# m_airconditioner_SCH.net
KiCad netlist of a schematic drawn in Altium Designer
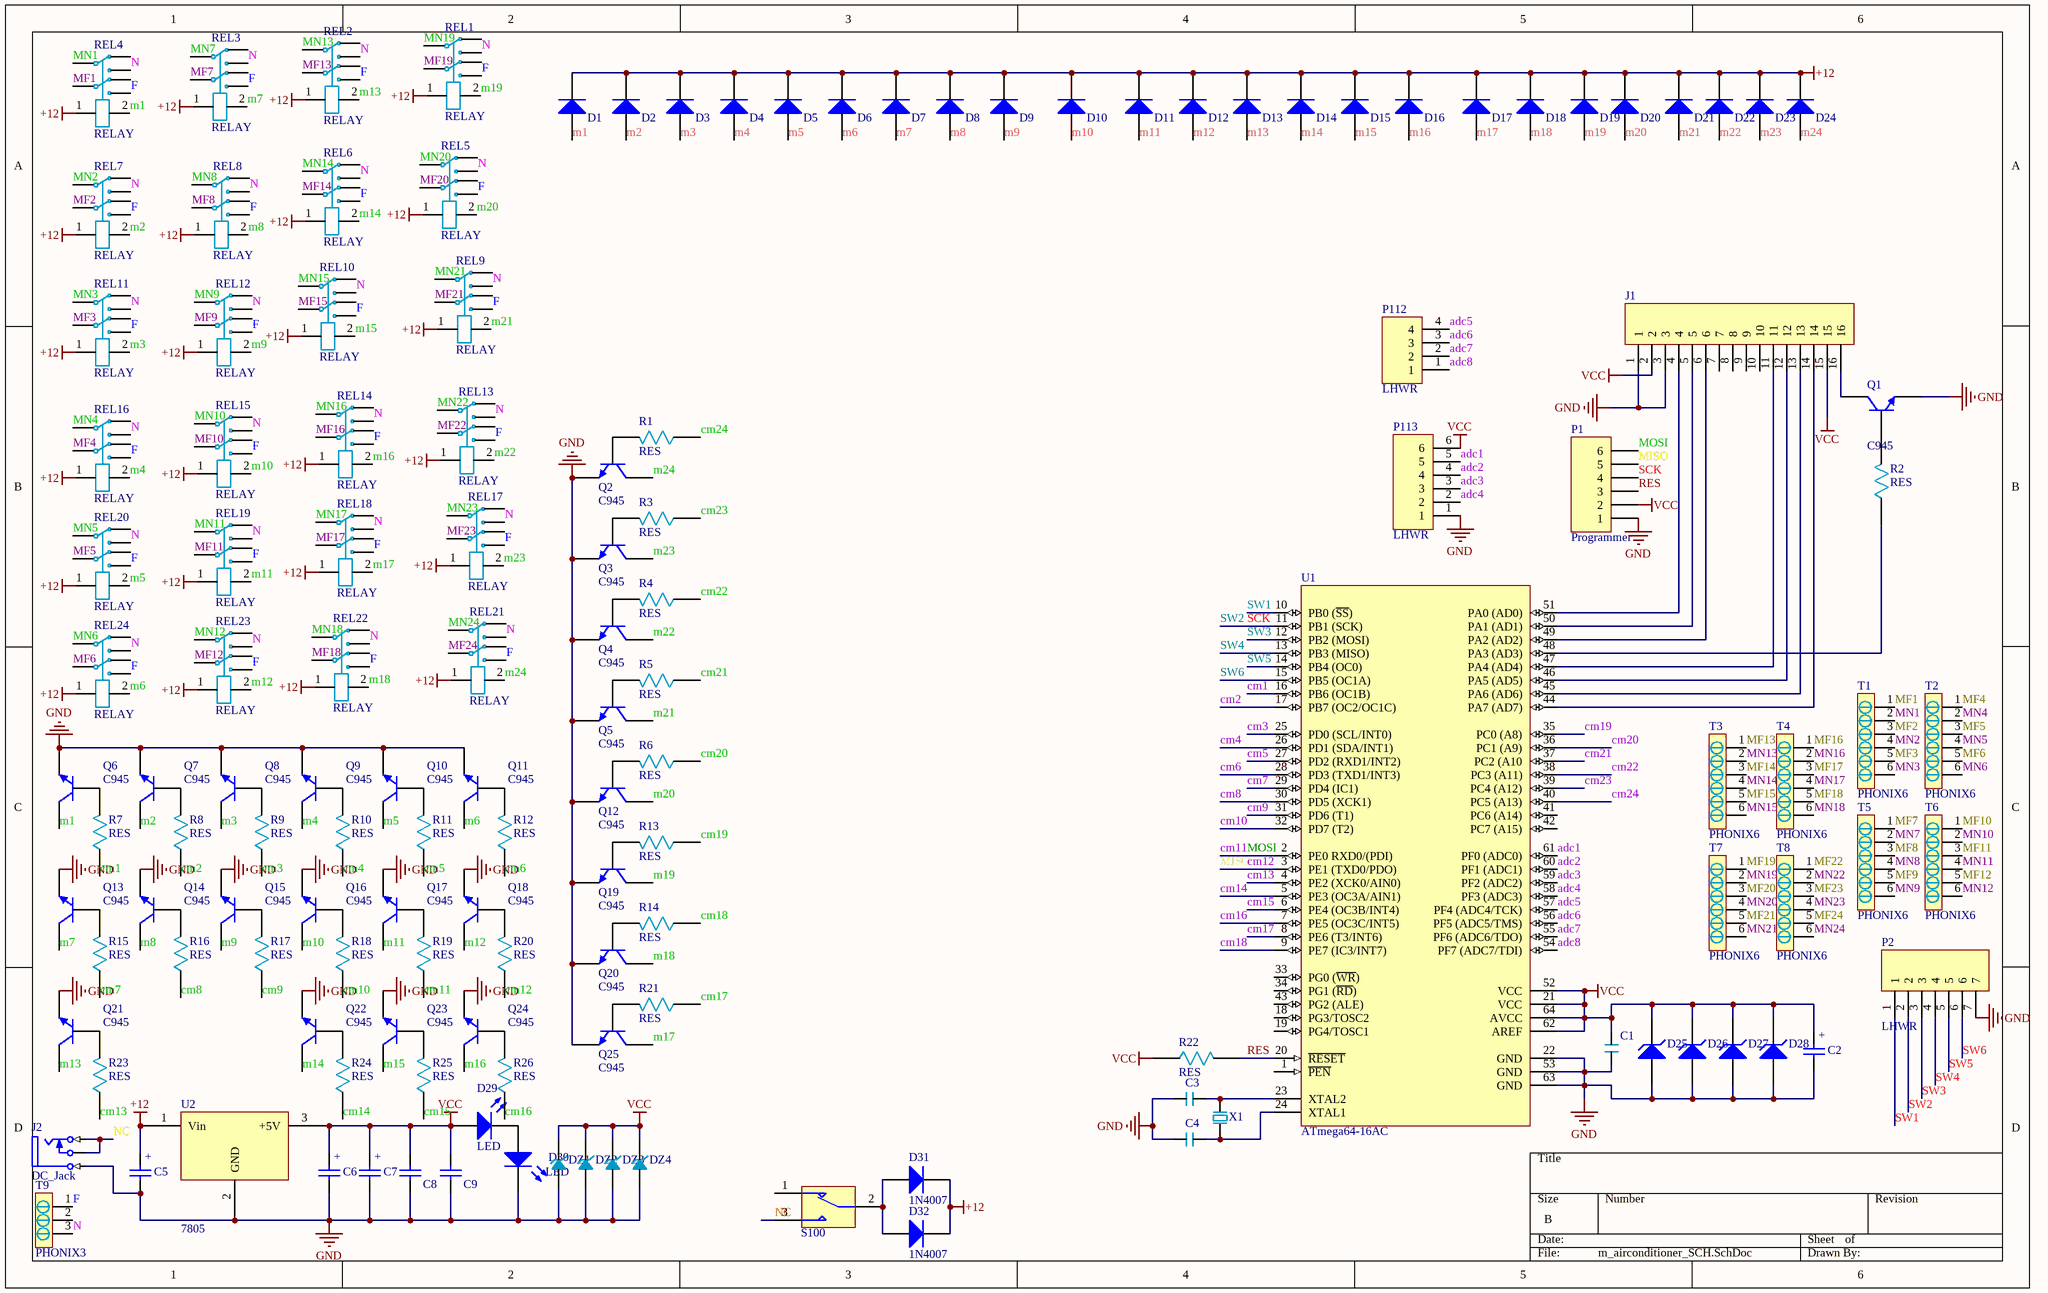
[diagram p0: m_airconditioner_SCH.SchDoc]

(export (version "E")
  (design (tool "Eeschema 10.0.6"))
  (components
    (comp (ref "C1") (value "~") (footprint "RAD_ADA") (libsource (lib "MyAltiumLib") (part "CAP")))
    (comp (ref "C2")
      (value "Cap")
      (footprint "My_cap3300u")
      (description "CAP-3300Uf")
      (libsource (lib "MyAltiumLib1") (part "Cap Pol"))
    )
    (comp (ref "C3") (value "CAP") (footprint "RAD_ADA") (libsource (lib "MyAltiumLib") (part "CAP")))
    (comp (ref "C4") (value "CAP") (footprint "RAD_ADA") (libsource (lib "MyAltiumLib") (part "CAP")))
    (comp (ref "C5")
      (value "Cap")
      (footprint "My_cap3300u")
      (description "CAP-3300Uf")
      (libsource (lib "MyAltiumLib1") (part "Cap Pol"))
    )
    (comp (ref "C6")
      (value "Cap")
      (footprint "My_cap3300u")
      (description "CAP-3300Uf")
      (libsource (lib "MyAltiumLib1") (part "Cap Pol"))
    )
    (comp (ref "C7")
      (value "Cap")
      (footprint "My_cap3300u")
      (description "CAP-3300Uf")
      (libsource (lib "MyAltiumLib1") (part "Cap Pol"))
    )
    (comp (ref "C8")
      (value "Cap")
      (footprint "My_cap100n")
      (description "CAP-100Nf")
      (libsource (lib "MyAltiumLib1") (part "Cap ceramic"))
    )
    (comp (ref "C9")
      (value "Cap")
      (footprint "My_cap100n")
      (description "CAP-100Nf")
      (libsource (lib "MyAltiumLib1") (part "Cap ceramic"))
    )
    (comp (ref "D1")
      (value "1N4007")
      (footprint "My_DO-41")
      (description "1 Amp Diode")
      (libsource (lib "MyAltiumLib1") (part "1N4007"))
    )
    (comp (ref "D2")
      (value "1N4007")
      (footprint "My_DO-41")
      (description "1 Amp Diode")
      (libsource (lib "MyAltiumLib1") (part "1N4007"))
    )
    (comp (ref "D3")
      (value "1N4007")
      (footprint "My_DO-41")
      (description "1 Amp Diode")
      (libsource (lib "MyAltiumLib1") (part "1N4007"))
    )
    (comp (ref "D4")
      (value "1N4007")
      (footprint "My_DO-41")
      (description "1 Amp Diode")
      (libsource (lib "MyAltiumLib1") (part "1N4007"))
    )
    (comp (ref "D5")
      (value "1N4007")
      (footprint "My_DO-41")
      (description "1 Amp Diode")
      (libsource (lib "MyAltiumLib1") (part "1N4007"))
    )
    (comp (ref "D6")
      (value "1N4007")
      (footprint "My_DO-41")
      (description "1 Amp Diode")
      (libsource (lib "MyAltiumLib1") (part "1N4007"))
    )
    (comp (ref "D7")
      (value "1N4007")
      (footprint "My_DO-41")
      (description "1 Amp Diode")
      (libsource (lib "MyAltiumLib1") (part "1N4007"))
    )
    (comp (ref "D8")
      (value "1N4007")
      (footprint "My_DO-41")
      (description "1 Amp Diode")
      (libsource (lib "MyAltiumLib1") (part "1N4007"))
    )
    (comp (ref "D9")
      (value "1N4007")
      (footprint "My_DO-41")
      (description "1 Amp Diode")
      (libsource (lib "MyAltiumLib1") (part "1N4007"))
    )
    (comp (ref "D10")
      (value "1N4007")
      (footprint "My_DO-41")
      (description "1 Amp Diode")
      (libsource (lib "MyAltiumLib1") (part "1N4007"))
    )
    (comp (ref "D11")
      (value "1N4007")
      (footprint "My_DO-41")
      (description "1 Amp Diode")
      (libsource (lib "MyAltiumLib1") (part "1N4007"))
    )
    (comp (ref "D12")
      (value "1N4007")
      (footprint "My_DO-41")
      (description "1 Amp Diode")
      (libsource (lib "MyAltiumLib1") (part "1N4007"))
    )
    (comp (ref "D13")
      (value "1N4007")
      (footprint "My_DO-41")
      (description "1 Amp Diode")
      (libsource (lib "MyAltiumLib1") (part "1N4007"))
    )
    (comp (ref "D14")
      (value "1N4007")
      (footprint "My_DO-41")
      (description "1 Amp Diode")
      (libsource (lib "MyAltiumLib1") (part "1N4007"))
    )
    (comp (ref "D15")
      (value "1N4007")
      (footprint "My_DO-41")
      (description "1 Amp Diode")
      (libsource (lib "MyAltiumLib1") (part "1N4007"))
    )
    (comp (ref "D16")
      (value "1N4007")
      (footprint "My_DO-41")
      (description "1 Amp Diode")
      (libsource (lib "MyAltiumLib1") (part "1N4007"))
    )
    (comp (ref "D17")
      (value "1N4007")
      (footprint "My_DO-41")
      (description "1 Amp Diode")
      (libsource (lib "MyAltiumLib1") (part "1N4007"))
    )
    (comp (ref "D18")
      (value "1N4007")
      (footprint "My_DO-41")
      (description "1 Amp Diode")
      (libsource (lib "MyAltiumLib1") (part "1N4007"))
    )
    (comp (ref "D19")
      (value "1N4007")
      (footprint "My_DO-41")
      (description "1 Amp Diode")
      (libsource (lib "MyAltiumLib1") (part "1N4007"))
    )
    (comp (ref "D20")
      (value "1N4007")
      (footprint "My_DO-41")
      (description "1 Amp Diode")
      (libsource (lib "MyAltiumLib1") (part "1N4007"))
    )
    (comp (ref "D21")
      (value "1N4007")
      (footprint "My_DO-41")
      (description "1 Amp Diode")
      (libsource (lib "MyAltiumLib1") (part "1N4007"))
    )
    (comp (ref "D22")
      (value "1N4007")
      (footprint "My_DO-41")
      (description "1 Amp Diode")
      (libsource (lib "MyAltiumLib1") (part "1N4007"))
    )
    (comp (ref "D23")
      (value "1N4007")
      (footprint "My_DO-41")
      (description "1 Amp Diode")
      (libsource (lib "MyAltiumLib1") (part "1N4007"))
    )
    (comp (ref "D24")
      (value "1N4007")
      (footprint "My_DO-41")
      (description "1 Amp Diode")
      (libsource (lib "MyAltiumLib1") (part "1N4007"))
    )
    (comp (ref "D25")
      (value "5V")
      (footprint "DIODE-0.7")
      (description "Zener Diode")
      (fields (field (name "PUBLISHER") "Altium Limited"))
      (libsource (lib "Miscellaneous Devices") (part "D Zener"))
    )
    (comp (ref "D26")
      (value "5v")
      (footprint "DIODE-0.7")
      (description "Zener Diode")
      (fields (field (name "PUBLISHER") "Altium Limited"))
      (libsource (lib "Miscellaneous Devices") (part "D Zener"))
    )
    (comp (ref "D27")
      (value "5V")
      (footprint "DIODE-0.7")
      (description "Zener Diode")
      (fields (field (name "PUBLISHER") "Altium Limited"))
      (libsource (lib "Miscellaneous Devices") (part "D Zener"))
    )
    (comp (ref "D28")
      (value "5V")
      (footprint "DIODE-0.7")
      (description "Zener Diode")
      (fields (field (name "PUBLISHER") "Altium Limited"))
      (libsource (lib "Miscellaneous Devices") (part "D Zener"))
    )
    (comp (ref "D29")
      (value "LED")
      (footprint "My_LED3MM")
      (description "Typical INFRARED GaAs LED")
      (fields (field (name "PUBLISHER") "Altium Limited"))
      (libsource (lib "MyAltiumLib1") (part "LED"))
    )
    (comp (ref "D30")
      (value "LED")
      (footprint "My_LED3MM")
      (description "Typical INFRARED GaAs LED")
      (fields (field (name "PUBLISHER") "Altium Limited"))
      (libsource (lib "MyAltiumLib1") (part "LED"))
    )
    (comp (ref "D31")
      (value "1N4007")
      (footprint "My_DO-41")
      (description "1 Amp Diode")
      (libsource (lib "MyAltiumLib1") (part "1N4007"))
    )
    (comp (ref "D32")
      (value "1N4007")
      (footprint "My_DO-41")
      (description "1 Amp Diode")
      (libsource (lib "MyAltiumLib1") (part "1N4007"))
    )
    (comp (ref "DZ1") (value "ZENER") (footprint "ZENER") (libsource (lib "MyAltiumLib") (part "ZENER")))
    (comp (ref "DZ2") (value "ZENER") (footprint "ZENER") (libsource (lib "MyAltiumLib") (part "ZENER")))
    (comp (ref "DZ3") (value "ZENER") (footprint "ZENER") (libsource (lib "MyAltiumLib") (part "ZENER")))
    (comp (ref "DZ4") (value "ZENER") (footprint "ZENER") (libsource (lib "MyAltiumLib") (part "ZENER")))
    (comp (ref "J1") (value "SIP16") (footprint "SIP16") (libsource (lib "My_lib_new") (part "SIP16")))
    (comp (ref "J2")
      (value "DC_Jack")
      (footprint "My_DC_Jack")
      (fields (field (name "PUBLISHER") "Altium Limited"))
      (libsource (lib "MyAltiumLib1") (part "DC_Jack"))
    )
    (comp (ref "P1")
      (value "Programmer")
      (footprint "HDR1X6")
      (description "Header, 6-Pin")
      (fields (field (name "PUBLISHER") "Altium Limited"))
      (libsource (lib "Miscellaneous Connectors") (part "Header 6"))
    )
    (comp (ref "P2")
      (value "LHWR")
      (footprint "Polarized Header 7")
      (fields (field (name "DESIGNER:") "Hamed Jafarzadeh - www.R2T.ir"))
      (libsource (lib "R2T Team Library") (part "7pin LHWR"))
    )
    (comp (ref "P112")
      (value "LHWR")
      (footprint "Polarized Header 4")
      (fields (field (name "DESIGNER:") "Hamed Jafarzadeh - www.R2T.ir"))
      (libsource (lib "R2T Team Library") (part "4pin LHWR"))
    )
    (comp (ref "P113")
      (value "LHWR")
      (footprint "Polarized Header 6")
      (fields (field (name "DESIGNER:") "Hamed Jafarzadeh - www.R2T.ir"))
      (libsource (lib "R2T Team Library") (part "6pin LHWR"))
    )
    (comp (ref "Q1")
      (value "C945")
      (footprint "C945")
      (description "NPN Transistor")
      (fields (field (name "DESIGNER") "Saeid Jorablo"))
      (libsource (lib "My Library") (part "C945"))
    )
    (comp (ref "Q2")
      (value "C945")
      (footprint "C945")
      (description "NPN Transistor")
      (fields (field (name "DESIGNER") "Saeid Jorablo"))
      (libsource (lib "My Library") (part "C945"))
    )
    (comp (ref "Q3")
      (value "C945")
      (footprint "C945")
      (description "NPN Transistor")
      (fields (field (name "DESIGNER") "Saeid Jorablo"))
      (libsource (lib "My Library") (part "C945"))
    )
    (comp (ref "Q4")
      (value "C945")
      (footprint "C945")
      (description "NPN Transistor")
      (fields (field (name "DESIGNER") "Saeid Jorablo"))
      (libsource (lib "My Library") (part "C945"))
    )
    (comp (ref "Q5")
      (value "C945")
      (footprint "C945")
      (description "NPN Transistor")
      (fields (field (name "DESIGNER") "Saeid Jorablo"))
      (libsource (lib "My Library") (part "C945"))
    )
    (comp (ref "Q6")
      (value "C945")
      (footprint "C945")
      (description "NPN Transistor")
      (fields (field (name "DESIGNER") "Saeid Jorablo"))
      (libsource (lib "My Library") (part "C945"))
    )
    (comp (ref "Q7")
      (value "C945")
      (footprint "C945")
      (description "NPN Transistor")
      (fields (field (name "DESIGNER") "Saeid Jorablo"))
      (libsource (lib "My Library") (part "C945"))
    )
    (comp (ref "Q8")
      (value "C945")
      (footprint "C945")
      (description "NPN Transistor")
      (fields (field (name "DESIGNER") "Saeid Jorablo"))
      (libsource (lib "My Library") (part "C945"))
    )
    (comp (ref "Q9")
      (value "C945")
      (footprint "C945")
      (description "NPN Transistor")
      (fields (field (name "DESIGNER") "Saeid Jorablo"))
      (libsource (lib "My Library") (part "C945"))
    )
    (comp (ref "Q10")
      (value "C945")
      (footprint "C945")
      (description "NPN Transistor")
      (fields (field (name "DESIGNER") "Saeid Jorablo"))
      (libsource (lib "My Library") (part "C945"))
    )
    (comp (ref "Q11")
      (value "C945")
      (footprint "C945")
      (description "NPN Transistor")
      (fields (field (name "DESIGNER") "Saeid Jorablo"))
      (libsource (lib "My Library") (part "C945"))
    )
    (comp (ref "Q12")
      (value "C945")
      (footprint "C945")
      (description "NPN Transistor")
      (fields (field (name "DESIGNER") "Saeid Jorablo"))
      (libsource (lib "My Library") (part "C945"))
    )
    (comp (ref "Q13")
      (value "C945")
      (footprint "C945")
      (description "NPN Transistor")
      (fields (field (name "DESIGNER") "Saeid Jorablo"))
      (libsource (lib "My Library") (part "C945"))
    )
    (comp (ref "Q14")
      (value "C945")
      (footprint "C945")
      (description "NPN Transistor")
      (fields (field (name "DESIGNER") "Saeid Jorablo"))
      (libsource (lib "My Library") (part "C945"))
    )
    (comp (ref "Q15")
      (value "C945")
      (footprint "C945")
      (description "NPN Transistor")
      (fields (field (name "DESIGNER") "Saeid Jorablo"))
      (libsource (lib "My Library") (part "C945"))
    )
    (comp (ref "Q16")
      (value "C945")
      (footprint "C945")
      (description "NPN Transistor")
      (fields (field (name "DESIGNER") "Saeid Jorablo"))
      (libsource (lib "My Library") (part "C945"))
    )
    (comp (ref "Q17")
      (value "C945")
      (footprint "C945")
      (description "NPN Transistor")
      (fields (field (name "DESIGNER") "Saeid Jorablo"))
      (libsource (lib "My Library") (part "C945"))
    )
    (comp (ref "Q18")
      (value "C945")
      (footprint "C945")
      (description "NPN Transistor")
      (fields (field (name "DESIGNER") "Saeid Jorablo"))
      (libsource (lib "My Library") (part "C945"))
    )
    (comp (ref "Q19")
      (value "C945")
      (footprint "C945")
      (description "NPN Transistor")
      (fields (field (name "DESIGNER") "Saeid Jorablo"))
      (libsource (lib "My Library") (part "C945"))
    )
    (comp (ref "Q20")
      (value "C945")
      (footprint "C945")
      (description "NPN Transistor")
      (fields (field (name "DESIGNER") "Saeid Jorablo"))
      (libsource (lib "My Library") (part "C945"))
    )
    (comp (ref "Q21")
      (value "C945")
      (footprint "C945")
      (description "NPN Transistor")
      (fields (field (name "DESIGNER") "Saeid Jorablo"))
      (libsource (lib "My Library") (part "C945"))
    )
    (comp (ref "Q22")
      (value "C945")
      (footprint "C945")
      (description "NPN Transistor")
      (fields (field (name "DESIGNER") "Saeid Jorablo"))
      (libsource (lib "My Library") (part "C945"))
    )
    (comp (ref "Q23")
      (value "C945")
      (footprint "C945")
      (description "NPN Transistor")
      (fields (field (name "DESIGNER") "Saeid Jorablo"))
      (libsource (lib "My Library") (part "C945"))
    )
    (comp (ref "Q24")
      (value "C945")
      (footprint "C945")
      (description "NPN Transistor")
      (fields (field (name "DESIGNER") "Saeid Jorablo"))
      (libsource (lib "My Library") (part "C945"))
    )
    (comp (ref "Q25")
      (value "C945")
      (footprint "C945")
      (description "NPN Transistor")
      (fields (field (name "DESIGNER") "Saeid Jorablo"))
      (libsource (lib "My Library") (part "C945"))
    )
    (comp (ref "R1") (value "RES") (footprint "AXIAL_V") (libsource (lib "MyAltiumLib") (part "RES")))
    (comp (ref "R2") (value "RES") (footprint "AXIAL0.4") (libsource (lib "My_lib_new") (part "RES")))
    (comp (ref "R3") (value "RES") (footprint "AXIAL_V") (libsource (lib "MyAltiumLib") (part "RES")))
    (comp (ref "R4") (value "RES") (footprint "AXIAL_V") (libsource (lib "MyAltiumLib") (part "RES")))
    (comp (ref "R5") (value "RES") (footprint "AXIAL_V") (libsource (lib "MyAltiumLib") (part "RES")))
    (comp (ref "R6") (value "RES") (footprint "AXIAL_V") (libsource (lib "MyAltiumLib") (part "RES")))
    (comp (ref "R7") (value "RES") (footprint "AXIAL_V") (libsource (lib "MyAltiumLib") (part "RES")))
    (comp (ref "R8") (value "RES") (footprint "AXIAL_V") (libsource (lib "MyAltiumLib") (part "RES")))
    (comp (ref "R9") (value "RES") (footprint "AXIAL_V") (libsource (lib "MyAltiumLib") (part "RES")))
    (comp (ref "R10") (value "RES") (footprint "AXIAL_V") (libsource (lib "MyAltiumLib") (part "RES")))
    (comp (ref "R11") (value "RES") (footprint "AXIAL_V") (libsource (lib "MyAltiumLib") (part "RES")))
    (comp (ref "R12") (value "RES") (footprint "AXIAL_V") (libsource (lib "MyAltiumLib") (part "RES")))
    (comp (ref "R13") (value "RES") (footprint "AXIAL_V") (libsource (lib "MyAltiumLib") (part "RES")))
    (comp (ref "R14") (value "RES") (footprint "AXIAL_V") (libsource (lib "MyAltiumLib") (part "RES")))
    (comp (ref "R15") (value "RES") (footprint "AXIAL_V") (libsource (lib "MyAltiumLib") (part "RES")))
    (comp (ref "R16") (value "RES") (footprint "AXIAL_V") (libsource (lib "MyAltiumLib") (part "RES")))
    (comp (ref "R17") (value "RES") (footprint "AXIAL_V") (libsource (lib "MyAltiumLib") (part "RES")))
    (comp (ref "R18") (value "RES") (footprint "AXIAL_V") (libsource (lib "MyAltiumLib") (part "RES")))
    (comp (ref "R19") (value "RES") (footprint "AXIAL_V") (libsource (lib "MyAltiumLib") (part "RES")))
    (comp (ref "R20") (value "RES") (footprint "AXIAL_V") (libsource (lib "MyAltiumLib") (part "RES")))
    (comp (ref "R21") (value "RES") (footprint "AXIAL_V") (libsource (lib "MyAltiumLib") (part "RES")))
    (comp (ref "R22") (value "RES") (footprint "AXIAL0.4") (libsource (lib "MyAltiumLib") (part "RES")))
    (comp (ref "R23") (value "RES") (footprint "AXIAL_V") (libsource (lib "MyAltiumLib") (part "RES")))
    (comp (ref "R24") (value "RES") (footprint "AXIAL_V") (libsource (lib "MyAltiumLib") (part "RES")))
    (comp (ref "R25") (value "RES") (footprint "AXIAL_V") (libsource (lib "MyAltiumLib") (part "RES")))
    (comp (ref "R26") (value "RES") (footprint "AXIAL_V") (libsource (lib "MyAltiumLib") (part "RES")))
    (comp (ref "REL1") (value "RELAY") (footprint "RELAY1") (libsource (lib "MyAltiumLib") (part "RELAY")))
    (comp (ref "REL2") (value "RELAY") (footprint "RELAY1") (libsource (lib "MyAltiumLib") (part "RELAY")))
    (comp (ref "REL3") (value "RELAY") (footprint "RELAY1") (libsource (lib "MyAltiumLib") (part "RELAY")))
    (comp (ref "REL4") (value "RELAY") (footprint "RELAY1") (libsource (lib "MyAltiumLib") (part "RELAY")))
    (comp (ref "REL5") (value "RELAY") (footprint "RELAY1") (libsource (lib "MyAltiumLib") (part "RELAY")))
    (comp (ref "REL6") (value "RELAY") (footprint "RELAY1") (libsource (lib "MyAltiumLib") (part "RELAY")))
    (comp (ref "REL7") (value "RELAY") (footprint "RELAY1") (libsource (lib "MyAltiumLib") (part "RELAY")))
    (comp (ref "REL8") (value "RELAY") (footprint "RELAY1") (libsource (lib "MyAltiumLib") (part "RELAY")))
    (comp (ref "REL9") (value "RELAY") (footprint "RELAY1") (libsource (lib "MyAltiumLib") (part "RELAY")))
    (comp (ref "REL10") (value "RELAY") (footprint "RELAY1") (libsource (lib "MyAltiumLib") (part "RELAY")))
    (comp (ref "REL11") (value "RELAY") (footprint "RELAY1") (libsource (lib "MyAltiumLib") (part "RELAY")))
    (comp (ref "REL12") (value "RELAY") (footprint "RELAY1") (libsource (lib "MyAltiumLib") (part "RELAY")))
    (comp (ref "REL13") (value "RELAY") (footprint "RELAY1") (libsource (lib "MyAltiumLib") (part "RELAY")))
    (comp (ref "REL14") (value "RELAY") (footprint "RELAY1") (libsource (lib "MyAltiumLib") (part "RELAY")))
    (comp (ref "REL15") (value "RELAY") (footprint "RELAY1") (libsource (lib "MyAltiumLib") (part "RELAY")))
    (comp (ref "REL16") (value "RELAY") (footprint "RELAY1") (libsource (lib "MyAltiumLib") (part "RELAY")))
    (comp (ref "REL17") (value "RELAY") (footprint "RELAY1") (libsource (lib "MyAltiumLib") (part "RELAY")))
    (comp (ref "REL18") (value "RELAY") (footprint "RELAY1") (libsource (lib "MyAltiumLib") (part "RELAY")))
    (comp (ref "REL19") (value "RELAY") (footprint "RELAY1") (libsource (lib "MyAltiumLib") (part "RELAY")))
    (comp (ref "REL20") (value "RELAY") (footprint "RELAY1") (libsource (lib "MyAltiumLib") (part "RELAY")))
    (comp (ref "REL21") (value "RELAY") (footprint "RELAY1") (libsource (lib "MyAltiumLib") (part "RELAY")))
    (comp (ref "REL22") (value "RELAY") (footprint "RELAY1") (libsource (lib "MyAltiumLib") (part "RELAY")))
    (comp (ref "REL23") (value "RELAY") (footprint "RELAY1") (libsource (lib "MyAltiumLib") (part "RELAY")))
    (comp (ref "REL24") (value "RELAY") (footprint "RELAY1") (libsource (lib "MyAltiumLib") (part "RELAY")))
    (comp (ref "S100")
      (value "Switch SPDT_Subminiator")
      (footprint "SPDT Subminiator")
      (description "Subminiator SPDT Switch")
      (libsource (lib "My Library") (part "Switch SPDT_Subminiator"))
    )
    (comp (ref "T1") (value "PHONIX6") (footprint "PHONIX6") (libsource (lib "MyAltiumLib") (part "PHONIX6")))
    (comp (ref "T2") (value "PHONIX6") (footprint "PHONIX6") (libsource (lib "MyAltiumLib") (part "PHONIX6")))
    (comp (ref "T3") (value "PHONIX6") (footprint "PHONIX6") (libsource (lib "MyAltiumLib") (part "PHONIX6")))
    (comp (ref "T4") (value "PHONIX6") (footprint "PHONIX6") (libsource (lib "MyAltiumLib") (part "PHONIX6")))
    (comp (ref "T5") (value "PHONIX6") (footprint "PHONIX6") (libsource (lib "MyAltiumLib") (part "PHONIX6")))
    (comp (ref "T6") (value "PHONIX6") (footprint "PHONIX6") (libsource (lib "MyAltiumLib") (part "PHONIX6")))
    (comp (ref "T7") (value "PHONIX6") (footprint "PHONIX6") (libsource (lib "MyAltiumLib") (part "PHONIX6")))
    (comp (ref "T8") (value "PHONIX6") (footprint "PHONIX6") (libsource (lib "MyAltiumLib") (part "PHONIX6")))
    (comp (ref "T9") (value "PHONIX3") (footprint "PHONIX3") (libsource (lib "MyAltiumLib") (part "PHONIX3")))
    (comp (ref "U1")
      (value "ATmega64-16AC")
      (footprint "64A_N")
      (description "8-Bit AVR Microcontroller with 64K Bytes of In-System Programmable Flash Memory")
      (fields (field (name "PUBLISHER") "Altium Limited"))
      (libsource (lib "Atmel Microcontroller 8-Bit AVR") (part "ATmega64-16AC"))
    )
    (comp (ref "U2")
      (value "7805")
      (footprint "My_TO-220")
      (description "Regulator")
      (libsource (lib "MyAltiumLib1") (part "7805"))
    )
    (comp (ref "X1") (value "XTAL") (footprint "XTAL_1") (libsource (lib "MyAltiumLib") (part "XTAL")))
  )
  (nets
    (net (code "1") (name "+12") (class "Default")
      (node (ref "C5") (pin "+") (pinfunction "+_+") (pintype "passive"))
      (node (ref "D1") (pin "K") (pinfunction "K_K") (pintype "passive"))
      (node (ref "D10") (pin "K") (pinfunction "K_K") (pintype "passive"))
      (node (ref "D11") (pin "K") (pinfunction "K_K") (pintype "passive"))
      (node (ref "D12") (pin "K") (pinfunction "K_K") (pintype "passive"))
      (node (ref "D13") (pin "K") (pinfunction "K_K") (pintype "passive"))
      (node (ref "D14") (pin "K") (pinfunction "K_K") (pintype "passive"))
      (node (ref "D15") (pin "K") (pinfunction "K_K") (pintype "passive"))
      (node (ref "D16") (pin "K") (pinfunction "K_K") (pintype "passive"))
      (node (ref "D17") (pin "K") (pinfunction "K_K") (pintype "passive"))
      (node (ref "D18") (pin "K") (pinfunction "K_K") (pintype "passive"))
      (node (ref "D19") (pin "K") (pinfunction "K_K") (pintype "passive"))
      (node (ref "D2") (pin "K") (pinfunction "K_K") (pintype "passive"))
      (node (ref "D20") (pin "K") (pinfunction "K_K") (pintype "passive"))
      (node (ref "D21") (pin "K") (pinfunction "K_K") (pintype "passive"))
      (node (ref "D22") (pin "K") (pinfunction "K_K") (pintype "passive"))
      (node (ref "D23") (pin "K") (pinfunction "K_K") (pintype "passive"))
      (node (ref "D24") (pin "K") (pinfunction "K_K") (pintype "passive"))
      (node (ref "D3") (pin "K") (pinfunction "K_K") (pintype "passive"))
      (node (ref "D31") (pin "K") (pinfunction "K_K") (pintype "passive"))
      (node (ref "D32") (pin "K") (pinfunction "K_K") (pintype "passive"))
      (node (ref "D4") (pin "K") (pinfunction "K_K") (pintype "passive"))
      (node (ref "D5") (pin "K") (pinfunction "K_K") (pintype "passive"))
      (node (ref "D6") (pin "K") (pinfunction "K_K") (pintype "passive"))
      (node (ref "D7") (pin "K") (pinfunction "K_K") (pintype "passive"))
      (node (ref "D8") (pin "K") (pinfunction "K_K") (pintype "passive"))
      (node (ref "D9") (pin "K") (pinfunction "K_K") (pintype "passive"))
      (node (ref "REL1") (pin "1") (pintype "passive"))
      (node (ref "REL10") (pin "1") (pintype "passive"))
      (node (ref "REL11") (pin "1") (pintype "passive"))
      (node (ref "REL12") (pin "1") (pintype "passive"))
      (node (ref "REL13") (pin "1") (pintype "passive"))
      (node (ref "REL14") (pin "1") (pintype "passive"))
      (node (ref "REL15") (pin "1") (pintype "passive"))
      (node (ref "REL16") (pin "1") (pintype "passive"))
      (node (ref "REL17") (pin "1") (pintype "passive"))
      (node (ref "REL18") (pin "1") (pintype "passive"))
      (node (ref "REL19") (pin "1") (pintype "passive"))
      (node (ref "REL2") (pin "1") (pintype "passive"))
      (node (ref "REL20") (pin "1") (pintype "passive"))
      (node (ref "REL21") (pin "1") (pintype "passive"))
      (node (ref "REL22") (pin "1") (pintype "passive"))
      (node (ref "REL23") (pin "1") (pintype "passive"))
      (node (ref "REL24") (pin "1") (pintype "passive"))
      (node (ref "REL3") (pin "1") (pintype "passive"))
      (node (ref "REL4") (pin "1") (pintype "passive"))
      (node (ref "REL5") (pin "1") (pintype "passive"))
      (node (ref "REL6") (pin "1") (pintype "passive"))
      (node (ref "REL7") (pin "1") (pintype "passive"))
      (node (ref "REL8") (pin "1") (pintype "passive"))
      (node (ref "REL9") (pin "1") (pintype "passive"))
      (node (ref "U2") (pin "1") (pinfunction "Vin_1") (pintype "power_in"))
    )
    (net (code "2") (name "/F") (class "Default")
      (node (ref "REL1") (pin "5") (pintype "passive"))
      (node (ref "REL10") (pin "5") (pintype "passive"))
      (node (ref "REL11") (pin "5") (pintype "passive"))
      (node (ref "REL12") (pin "5") (pintype "passive"))
      (node (ref "REL13") (pin "5") (pintype "passive"))
      (node (ref "REL14") (pin "5") (pintype "passive"))
      (node (ref "REL15") (pin "5") (pintype "passive"))
      (node (ref "REL16") (pin "5") (pintype "passive"))
      (node (ref "REL17") (pin "5") (pintype "passive"))
      (node (ref "REL18") (pin "5") (pintype "passive"))
      (node (ref "REL19") (pin "5") (pintype "passive"))
      (node (ref "REL2") (pin "5") (pintype "passive"))
      (node (ref "REL20") (pin "5") (pintype "passive"))
      (node (ref "REL21") (pin "5") (pintype "passive"))
      (node (ref "REL22") (pin "5") (pintype "passive"))
      (node (ref "REL23") (pin "5") (pintype "passive"))
      (node (ref "REL24") (pin "5") (pintype "passive"))
      (node (ref "REL3") (pin "5") (pintype "passive"))
      (node (ref "REL4") (pin "5") (pintype "passive"))
      (node (ref "REL5") (pin "5") (pintype "passive"))
      (node (ref "REL6") (pin "5") (pintype "passive"))
      (node (ref "REL7") (pin "5") (pintype "passive"))
      (node (ref "REL8") (pin "5") (pintype "passive"))
      (node (ref "REL9") (pin "5") (pintype "passive"))
      (node (ref "T9") (pin "1") (pintype "passive"))
    )
    (net (code "3") (name "/MF1") (class "Default")
      (node (ref "REL4") (pin "3") (pintype "passive"))
      (node (ref "T1") (pin "1") (pintype "passive"))
    )
    (net (code "4") (name "/MF2") (class "Default")
      (node (ref "REL7") (pin "3") (pintype "passive"))
      (node (ref "T1") (pin "3") (pintype "passive"))
    )
    (net (code "5") (name "/MF3") (class "Default")
      (node (ref "REL11") (pin "3") (pintype "passive"))
      (node (ref "T1") (pin "5") (pintype "passive"))
    )
    (net (code "6") (name "/MF4") (class "Default")
      (node (ref "REL16") (pin "3") (pintype "passive"))
      (node (ref "T2") (pin "1") (pintype "passive"))
    )
    (net (code "7") (name "/MF5") (class "Default")
      (node (ref "REL20") (pin "3") (pintype "passive"))
      (node (ref "T2") (pin "3") (pintype "passive"))
    )
    (net (code "8") (name "/MF6") (class "Default")
      (node (ref "REL24") (pin "3") (pintype "passive"))
      (node (ref "T2") (pin "5") (pintype "passive"))
    )
    (net (code "9") (name "/MF7") (class "Default")
      (node (ref "REL3") (pin "3") (pintype "passive"))
      (node (ref "T5") (pin "1") (pintype "passive"))
    )
    (net (code "10") (name "/MF8") (class "Default")
      (node (ref "REL8") (pin "3") (pintype "passive"))
      (node (ref "T5") (pin "3") (pintype "passive"))
    )
    (net (code "11") (name "/MF9") (class "Default")
      (node (ref "REL12") (pin "3") (pintype "passive"))
      (node (ref "T5") (pin "5") (pintype "passive"))
    )
    (net (code "12") (name "/MF10") (class "Default")
      (node (ref "REL15") (pin "3") (pintype "passive"))
      (node (ref "T6") (pin "1") (pintype "passive"))
    )
    (net (code "13") (name "/MF11") (class "Default")
      (node (ref "REL19") (pin "3") (pintype "passive"))
      (node (ref "T6") (pin "3") (pintype "passive"))
    )
    (net (code "14") (name "/MF12") (class "Default")
      (node (ref "REL23") (pin "3") (pintype "passive"))
      (node (ref "T6") (pin "5") (pintype "passive"))
    )
    (net (code "15") (name "/MF13") (class "Default")
      (node (ref "REL2") (pin "3") (pintype "passive"))
      (node (ref "T3") (pin "1") (pintype "passive"))
    )
    (net (code "16") (name "/MF14") (class "Default")
      (node (ref "REL6") (pin "3") (pintype "passive"))
      (node (ref "T3") (pin "3") (pintype "passive"))
    )
    (net (code "17") (name "/MF15") (class "Default")
      (node (ref "REL10") (pin "3") (pintype "passive"))
      (node (ref "T3") (pin "5") (pintype "passive"))
    )
    (net (code "18") (name "/MF16") (class "Default")
      (node (ref "REL14") (pin "3") (pintype "passive"))
      (node (ref "T4") (pin "1") (pintype "passive"))
    )
    (net (code "19") (name "/MF17") (class "Default")
      (node (ref "REL18") (pin "3") (pintype "passive"))
      (node (ref "T4") (pin "3") (pintype "passive"))
    )
    (net (code "20") (name "/MF18") (class "Default")
      (node (ref "REL22") (pin "3") (pintype "passive"))
      (node (ref "T4") (pin "5") (pintype "passive"))
    )
    (net (code "21") (name "/MF19") (class "Default")
      (node (ref "REL1") (pin "3") (pintype "passive"))
      (node (ref "T7") (pin "1") (pintype "passive"))
    )
    (net (code "22") (name "/MF20") (class "Default")
      (node (ref "REL5") (pin "3") (pintype "passive"))
      (node (ref "T7") (pin "3") (pintype "passive"))
    )
    (net (code "23") (name "/MF21") (class "Default")
      (node (ref "REL9") (pin "3") (pintype "passive"))
      (node (ref "T7") (pin "5") (pintype "passive"))
    )
    (net (code "24") (name "/MF22") (class "Default")
      (node (ref "REL13") (pin "3") (pintype "passive"))
      (node (ref "T8") (pin "1") (pintype "passive"))
    )
    (net (code "25") (name "/MF23") (class "Default")
      (node (ref "REL17") (pin "3") (pintype "passive"))
      (node (ref "T8") (pin "3") (pintype "passive"))
    )
    (net (code "26") (name "/MF24") (class "Default")
      (node (ref "REL21") (pin "3") (pintype "passive"))
      (node (ref "T8") (pin "5") (pintype "passive"))
    )
    (net (code "27") (name "/MISO") (class "Default")
      (node (ref "P1") (pin "5") (pinfunction "5_5") (pintype "passive"))
      (node (ref "R20") (pin "1") (pintype "passive"))
      (node (ref "U1") (pin "3") (pinfunction "PE1_(TXD0/PDO)_3") (pintype "bidirectional"))
    )
    (net (code "28") (name "/MN1") (class "Default")
      (node (ref "REL4") (pin "4") (pintype "passive"))
      (node (ref "T1") (pin "2") (pintype "passive"))
    )
    (net (code "29") (name "/MN2") (class "Default")
      (node (ref "REL7") (pin "4") (pintype "passive"))
      (node (ref "T1") (pin "4") (pintype "passive"))
    )
    (net (code "30") (name "/MN3") (class "Default")
      (node (ref "REL11") (pin "4") (pintype "passive"))
      (node (ref "T1") (pin "6") (pintype "passive"))
    )
    (net (code "31") (name "/MN4") (class "Default")
      (node (ref "REL16") (pin "4") (pintype "passive"))
      (node (ref "T2") (pin "2") (pintype "passive"))
    )
    (net (code "32") (name "/MN5") (class "Default")
      (node (ref "REL20") (pin "4") (pintype "passive"))
      (node (ref "T2") (pin "4") (pintype "passive"))
    )
    (net (code "33") (name "/MN6") (class "Default")
      (node (ref "REL24") (pin "4") (pintype "passive"))
      (node (ref "T2") (pin "6") (pintype "passive"))
    )
    (net (code "34") (name "/MN7") (class "Default")
      (node (ref "REL3") (pin "4") (pintype "passive"))
      (node (ref "T5") (pin "2") (pintype "passive"))
    )
    (net (code "35") (name "/MN8") (class "Default")
      (node (ref "REL8") (pin "4") (pintype "passive"))
      (node (ref "T5") (pin "4") (pintype "passive"))
    )
    (net (code "36") (name "/MN9") (class "Default")
      (node (ref "REL12") (pin "4") (pintype "passive"))
      (node (ref "T5") (pin "6") (pintype "passive"))
    )
    (net (code "37") (name "/MN10") (class "Default")
      (node (ref "REL15") (pin "4") (pintype "passive"))
      (node (ref "T6") (pin "2") (pintype "passive"))
    )
    (net (code "38") (name "/MN11") (class "Default")
      (node (ref "REL19") (pin "4") (pintype "passive"))
      (node (ref "T6") (pin "4") (pintype "passive"))
    )
    (net (code "39") (name "/MN12") (class "Default")
      (node (ref "REL23") (pin "4") (pintype "passive"))
      (node (ref "T6") (pin "6") (pintype "passive"))
    )
    (net (code "40") (name "/MN13") (class "Default")
      (node (ref "REL2") (pin "4") (pintype "passive"))
      (node (ref "T3") (pin "2") (pintype "passive"))
    )
    (net (code "41") (name "/MN14") (class "Default")
      (node (ref "REL6") (pin "4") (pintype "passive"))
      (node (ref "T3") (pin "4") (pintype "passive"))
    )
    (net (code "42") (name "/MN15") (class "Default")
      (node (ref "REL10") (pin "4") (pintype "passive"))
      (node (ref "T3") (pin "6") (pintype "passive"))
    )
    (net (code "43") (name "/MN16") (class "Default")
      (node (ref "REL14") (pin "4") (pintype "passive"))
      (node (ref "T4") (pin "2") (pintype "passive"))
    )
    (net (code "44") (name "/MN17") (class "Default")
      (node (ref "REL18") (pin "4") (pintype "passive"))
      (node (ref "T4") (pin "4") (pintype "passive"))
    )
    (net (code "45") (name "/MN18") (class "Default")
      (node (ref "REL22") (pin "4") (pintype "passive"))
      (node (ref "T4") (pin "6") (pintype "passive"))
    )
    (net (code "46") (name "/MN19") (class "Default")
      (node (ref "REL1") (pin "4") (pintype "passive"))
      (node (ref "T7") (pin "2") (pintype "passive"))
    )
    (net (code "47") (name "/MN20") (class "Default")
      (node (ref "REL5") (pin "4") (pintype "passive"))
      (node (ref "T7") (pin "4") (pintype "passive"))
    )
    (net (code "48") (name "/MN21") (class "Default")
      (node (ref "REL9") (pin "4") (pintype "passive"))
      (node (ref "T7") (pin "6") (pintype "passive"))
    )
    (net (code "49") (name "/MN22") (class "Default")
      (node (ref "REL13") (pin "4") (pintype "passive"))
      (node (ref "T8") (pin "2") (pintype "passive"))
    )
    (net (code "50") (name "/MN23") (class "Default")
      (node (ref "REL17") (pin "4") (pintype "passive"))
      (node (ref "T8") (pin "4") (pintype "passive"))
    )
    (net (code "51") (name "/MN24") (class "Default")
      (node (ref "REL21") (pin "4") (pintype "passive"))
      (node (ref "T8") (pin "6") (pintype "passive"))
    )
    (net (code "52") (name "/MOSI") (class "Default")
      (node (ref "P1") (pin "6") (pinfunction "6_6") (pintype "passive"))
      (node (ref "R19") (pin "1") (pintype "passive"))
      (node (ref "U1") (pin "2") (pinfunction "PE0_RXD0/(PDI)_2") (pintype "bidirectional"))
    )
    (net (code "53") (name "/N") (class "Default")
      (node (ref "REL1") (pin "7") (pintype "passive"))
      (node (ref "REL10") (pin "7") (pintype "passive"))
      (node (ref "REL11") (pin "7") (pintype "passive"))
      (node (ref "REL12") (pin "7") (pintype "passive"))
      (node (ref "REL13") (pin "7") (pintype "passive"))
      (node (ref "REL14") (pin "7") (pintype "passive"))
      (node (ref "REL15") (pin "7") (pintype "passive"))
      (node (ref "REL16") (pin "7") (pintype "passive"))
      (node (ref "REL17") (pin "7") (pintype "passive"))
      (node (ref "REL18") (pin "7") (pintype "passive"))
      (node (ref "REL19") (pin "7") (pintype "passive"))
      (node (ref "REL2") (pin "7") (pintype "passive"))
      (node (ref "REL20") (pin "7") (pintype "passive"))
      (node (ref "REL21") (pin "7") (pintype "passive"))
      (node (ref "REL22") (pin "7") (pintype "passive"))
      (node (ref "REL23") (pin "7") (pintype "passive"))
      (node (ref "REL24") (pin "7") (pintype "passive"))
      (node (ref "REL3") (pin "7") (pintype "passive"))
      (node (ref "REL4") (pin "7") (pintype "passive"))
      (node (ref "REL5") (pin "7") (pintype "passive"))
      (node (ref "REL6") (pin "7") (pintype "passive"))
      (node (ref "REL7") (pin "7") (pintype "passive"))
      (node (ref "REL8") (pin "7") (pintype "passive"))
      (node (ref "REL9") (pin "7") (pintype "passive"))
      (node (ref "T9") (pin "3") (pintype "passive"))
    )
    (net (code "54") (name "/NC") (class "Default")
      (node (ref "J2") (pin "1") (pinfunction "T_1") (pintype "input"))
      (node (ref "J2") (pin "2") (pinfunction "TN_2") (pintype "passive"))
      (node (ref "S100") (pin "3") (pinfunction "3_3") (pintype "passive"))
    )
    (net (code "55") (name "/RES") (class "Default")
      (node (ref "P1") (pin "3") (pinfunction "3_3") (pintype "passive"))
      (node (ref "R22") (pin "2") (pintype "passive"))
      (node (ref "U1") (pin "20") (pinfunction "~{RESET}_20") (pintype "input"))
    )
    (net (code "56") (name "/SCK") (class "Default")
      (node (ref "P1") (pin "4") (pinfunction "4_4") (pintype "passive"))
      (node (ref "P2") (pin "2") (pinfunction "2_2") (pintype "passive"))
      (node (ref "U1") (pin "11") (pinfunction "PB1_(SCK)_11") (pintype "bidirectional"))
    )
    (net (code "57") (name "/SW1") (class "Default")
      (node (ref "P2") (pin "1") (pinfunction "1_1") (pintype "passive"))
      (node (ref "U1") (pin "10") (pinfunction "PB0_(~{SS})_10") (pintype "bidirectional"))
    )
    (net (code "58") (name "/SW3") (class "Default")
      (node (ref "P2") (pin "3") (pinfunction "3_3") (pintype "passive"))
      (node (ref "U1") (pin "12") (pinfunction "PB2_(MOSI)_12") (pintype "bidirectional"))
    )
    (net (code "59") (name "/SW4") (class "Default")
      (node (ref "P2") (pin "4") (pinfunction "4_4") (pintype "passive"))
      (node (ref "U1") (pin "13") (pinfunction "PB3_(MISO)_13") (pintype "bidirectional"))
    )
    (net (code "60") (name "/SW5") (class "Default")
      (node (ref "P2") (pin "5") (pinfunction "5_5") (pintype "passive"))
      (node (ref "U1") (pin "14") (pinfunction "PB4_(OC0)_14") (pintype "bidirectional"))
    )
    (net (code "61") (name "/SW6") (class "Default")
      (node (ref "P2") (pin "6") (pinfunction "6_6") (pintype "passive"))
      (node (ref "U1") (pin "15") (pinfunction "PB5_(OC1A)_15") (pintype "bidirectional"))
    )
    (net (code "62") (name "/adc1") (class "Default")
      (node (ref "P113") (pin "5") (pinfunction "5_5") (pintype "passive"))
      (node (ref "U1") (pin "61") (pinfunction "PF0_(ADC0)_61") (pintype "bidirectional"))
    )
    (net (code "63") (name "/adc2") (class "Default")
      (node (ref "P113") (pin "4") (pinfunction "4_4") (pintype "passive"))
      (node (ref "U1") (pin "60") (pinfunction "PF1_(ADC1)_60") (pintype "bidirectional"))
    )
    (net (code "64") (name "/adc3") (class "Default")
      (node (ref "P113") (pin "3") (pinfunction "3_3") (pintype "passive"))
      (node (ref "U1") (pin "59") (pinfunction "PF2_(ADC2)_59") (pintype "bidirectional"))
    )
    (net (code "65") (name "/adc4") (class "Default")
      (node (ref "P113") (pin "2") (pinfunction "2_2") (pintype "passive"))
      (node (ref "U1") (pin "58") (pinfunction "PF3_(ADC3)_58") (pintype "bidirectional"))
    )
    (net (code "66") (name "/adc5") (class "Default")
      (node (ref "P112") (pin "4") (pinfunction "4_4") (pintype "passive"))
      (node (ref "U1") (pin "57") (pinfunction "PF4_(ADC4/TCK)_57") (pintype "bidirectional"))
    )
    (net (code "67") (name "/adc6") (class "Default")
      (node (ref "P112") (pin "3") (pinfunction "3_3") (pintype "passive"))
      (node (ref "U1") (pin "56") (pinfunction "PF5_(ADC5/TMS)_56") (pintype "bidirectional"))
    )
    (net (code "68") (name "/adc7") (class "Default")
      (node (ref "P112") (pin "2") (pinfunction "2_2") (pintype "passive"))
      (node (ref "U1") (pin "55") (pinfunction "PF6_(ADC6/TDO)_55") (pintype "bidirectional"))
    )
    (net (code "69") (name "/adc8") (class "Default")
      (node (ref "P112") (pin "1") (pinfunction "1_1") (pintype "passive"))
      (node (ref "U1") (pin "54") (pinfunction "PF7_(ADC7/TDI)_54") (pintype "bidirectional"))
    )
    (net (code "70") (name "/cm1") (class "Default")
      (node (ref "R7") (pin "1") (pintype "passive"))
      (node (ref "U1") (pin "16") (pinfunction "PB6_(OC1B)_16") (pintype "bidirectional"))
    )
    (net (code "71") (name "/cm2") (class "Default")
      (node (ref "R8") (pin "1") (pintype "passive"))
      (node (ref "U1") (pin "17") (pinfunction "PB7_(OC2/OC1C)_17") (pintype "bidirectional"))
    )
    (net (code "72") (name "/cm3") (class "Default")
      (node (ref "R9") (pin "1") (pintype "passive"))
      (node (ref "U1") (pin "25") (pinfunction "PD0_(SCL/INT0)_25") (pintype "bidirectional"))
    )
    (net (code "73") (name "/cm4") (class "Default")
      (node (ref "R10") (pin "1") (pintype "passive"))
      (node (ref "U1") (pin "26") (pinfunction "PD1_(SDA/INT1)_26") (pintype "bidirectional"))
    )
    (net (code "74") (name "/cm5") (class "Default")
      (node (ref "R11") (pin "1") (pintype "passive"))
      (node (ref "U1") (pin "27") (pinfunction "PD2_(RXD1/INT2)_27") (pintype "bidirectional"))
    )
    (net (code "75") (name "/cm6") (class "Default")
      (node (ref "R12") (pin "1") (pintype "passive"))
      (node (ref "U1") (pin "28") (pinfunction "PD3_(TXD1/INT3)_28") (pintype "bidirectional"))
    )
    (net (code "76") (name "/cm7") (class "Default")
      (node (ref "R15") (pin "1") (pintype "passive"))
      (node (ref "U1") (pin "29") (pinfunction "PD4_(IC1)_29") (pintype "bidirectional"))
    )
    (net (code "77") (name "/cm8") (class "Default")
      (node (ref "R16") (pin "1") (pintype "passive"))
      (node (ref "U1") (pin "30") (pinfunction "PD5_(XCK1)_30") (pintype "bidirectional"))
    )
    (net (code "78") (name "/cm9") (class "Default")
      (node (ref "R17") (pin "1") (pintype "passive"))
      (node (ref "U1") (pin "31") (pinfunction "PD6_(T1)_31") (pintype "bidirectional"))
    )
    (net (code "79") (name "/cm10") (class "Default")
      (node (ref "R18") (pin "1") (pintype "passive"))
      (node (ref "U1") (pin "32") (pinfunction "PD7_(T2)_32") (pintype "bidirectional"))
    )
    (net (code "80") (name "/cm13") (class "Default")
      (node (ref "R23") (pin "1") (pintype "passive"))
      (node (ref "U1") (pin "4") (pinfunction "PE2_(XCK0/AIN0)_4") (pintype "bidirectional"))
    )
    (net (code "81") (name "/cm14") (class "Default")
      (node (ref "R24") (pin "1") (pintype "passive"))
      (node (ref "U1") (pin "5") (pinfunction "PE3_(OC3A/AIN1)_5") (pintype "bidirectional"))
    )
    (net (code "82") (name "/cm15") (class "Default")
      (node (ref "R25") (pin "1") (pintype "passive"))
      (node (ref "U1") (pin "6") (pinfunction "PE4_(OC3B/INT4)_6") (pintype "bidirectional"))
    )
    (net (code "83") (name "/cm16") (class "Default")
      (node (ref "R26") (pin "1") (pintype "passive"))
      (node (ref "U1") (pin "7") (pinfunction "PE5_(OC3C/INT5)_7") (pintype "bidirectional"))
    )
    (net (code "84") (name "/cm17") (class "Default")
      (node (ref "R21") (pin "1") (pintype "passive"))
      (node (ref "U1") (pin "8") (pinfunction "PE6_(T3/INT6)_8") (pintype "bidirectional"))
    )
    (net (code "85") (name "/cm18") (class "Default")
      (node (ref "R14") (pin "1") (pintype "passive"))
      (node (ref "U1") (pin "9") (pinfunction "PE7_(IC3/INT7)_9") (pintype "bidirectional"))
    )
    (net (code "86") (name "/cm19") (class "Default")
      (node (ref "R13") (pin "1") (pintype "passive"))
      (node (ref "U1") (pin "35") (pinfunction "PC0_(A8)_35") (pintype "bidirectional"))
    )
    (net (code "87") (name "/cm20") (class "Default")
      (node (ref "R6") (pin "1") (pintype "passive"))
      (node (ref "U1") (pin "36") (pinfunction "PC1_(A9)_36") (pintype "bidirectional"))
    )
    (net (code "88") (name "/cm21") (class "Default")
      (node (ref "R5") (pin "1") (pintype "passive"))
      (node (ref "U1") (pin "37") (pinfunction "PC2_(A10_37") (pintype "bidirectional"))
    )
    (net (code "89") (name "/cm22") (class "Default")
      (node (ref "R4") (pin "1") (pintype "passive"))
      (node (ref "U1") (pin "38") (pinfunction "PC3_(A11)_38") (pintype "bidirectional"))
    )
    (net (code "90") (name "/cm23") (class "Default")
      (node (ref "R3") (pin "1") (pintype "passive"))
      (node (ref "U1") (pin "39") (pinfunction "PC4_(A12)_39") (pintype "bidirectional"))
    )
    (net (code "91") (name "/cm24") (class "Default")
      (node (ref "R1") (pin "1") (pintype "passive"))
      (node (ref "U1") (pin "40") (pinfunction "PC5_(A13)_40") (pintype "bidirectional"))
    )
    (net (code "92") (name "/m1") (class "Default")
      (node (ref "D1") (pin "A") (pinfunction "A_A") (pintype "passive"))
      (node (ref "Q6") (pin "2") (pinfunction "C_2") (pintype "passive"))
      (node (ref "REL4") (pin "2") (pintype "passive"))
    )
    (net (code "93") (name "/m2") (class "Default")
      (node (ref "D2") (pin "A") (pinfunction "A_A") (pintype "passive"))
      (node (ref "Q7") (pin "2") (pinfunction "C_2") (pintype "passive"))
      (node (ref "REL7") (pin "2") (pintype "passive"))
    )
    (net (code "94") (name "/m3") (class "Default")
      (node (ref "D3") (pin "A") (pinfunction "A_A") (pintype "passive"))
      (node (ref "Q8") (pin "2") (pinfunction "C_2") (pintype "passive"))
      (node (ref "REL11") (pin "2") (pintype "passive"))
    )
    (net (code "95") (name "/m4") (class "Default")
      (node (ref "D4") (pin "A") (pinfunction "A_A") (pintype "passive"))
      (node (ref "Q9") (pin "2") (pinfunction "C_2") (pintype "passive"))
      (node (ref "REL16") (pin "2") (pintype "passive"))
    )
    (net (code "96") (name "/m5") (class "Default")
      (node (ref "D5") (pin "A") (pinfunction "A_A") (pintype "passive"))
      (node (ref "Q10") (pin "2") (pinfunction "C_2") (pintype "passive"))
      (node (ref "REL20") (pin "2") (pintype "passive"))
    )
    (net (code "97") (name "/m6") (class "Default")
      (node (ref "D6") (pin "A") (pinfunction "A_A") (pintype "passive"))
      (node (ref "Q11") (pin "2") (pinfunction "C_2") (pintype "passive"))
      (node (ref "REL24") (pin "2") (pintype "passive"))
    )
    (net (code "98") (name "/m7") (class "Default")
      (node (ref "D7") (pin "A") (pinfunction "A_A") (pintype "passive"))
      (node (ref "Q13") (pin "2") (pinfunction "C_2") (pintype "passive"))
      (node (ref "REL3") (pin "2") (pintype "passive"))
    )
    (net (code "99") (name "/m8") (class "Default")
      (node (ref "D8") (pin "A") (pinfunction "A_A") (pintype "passive"))
      (node (ref "Q14") (pin "2") (pinfunction "C_2") (pintype "passive"))
      (node (ref "REL8") (pin "2") (pintype "passive"))
    )
    (net (code "100") (name "/m9") (class "Default")
      (node (ref "D9") (pin "A") (pinfunction "A_A") (pintype "passive"))
      (node (ref "Q15") (pin "2") (pinfunction "C_2") (pintype "passive"))
      (node (ref "REL12") (pin "2") (pintype "passive"))
    )
    (net (code "101") (name "/m10") (class "Default")
      (node (ref "D10") (pin "A") (pinfunction "A_A") (pintype "passive"))
      (node (ref "Q16") (pin "2") (pinfunction "C_2") (pintype "passive"))
      (node (ref "REL15") (pin "2") (pintype "passive"))
    )
    (net (code "102") (name "/m11") (class "Default")
      (node (ref "D11") (pin "A") (pinfunction "A_A") (pintype "passive"))
      (node (ref "Q17") (pin "2") (pinfunction "C_2") (pintype "passive"))
      (node (ref "REL19") (pin "2") (pintype "passive"))
    )
    (net (code "103") (name "/m12") (class "Default")
      (node (ref "D12") (pin "A") (pinfunction "A_A") (pintype "passive"))
      (node (ref "Q18") (pin "2") (pinfunction "C_2") (pintype "passive"))
      (node (ref "REL23") (pin "2") (pintype "passive"))
    )
    (net (code "104") (name "/m13") (class "Default")
      (node (ref "D13") (pin "A") (pinfunction "A_A") (pintype "passive"))
      (node (ref "Q21") (pin "2") (pinfunction "C_2") (pintype "passive"))
      (node (ref "REL2") (pin "2") (pintype "passive"))
    )
    (net (code "105") (name "/m14") (class "Default")
      (node (ref "D14") (pin "A") (pinfunction "A_A") (pintype "passive"))
      (node (ref "Q22") (pin "2") (pinfunction "C_2") (pintype "passive"))
      (node (ref "REL6") (pin "2") (pintype "passive"))
    )
    (net (code "106") (name "/m15") (class "Default")
      (node (ref "D15") (pin "A") (pinfunction "A_A") (pintype "passive"))
      (node (ref "Q23") (pin "2") (pinfunction "C_2") (pintype "passive"))
      (node (ref "REL10") (pin "2") (pintype "passive"))
    )
    (net (code "107") (name "/m16") (class "Default")
      (node (ref "D16") (pin "A") (pinfunction "A_A") (pintype "passive"))
      (node (ref "Q24") (pin "2") (pinfunction "C_2") (pintype "passive"))
      (node (ref "REL14") (pin "2") (pintype "passive"))
    )
    (net (code "108") (name "/m17") (class "Default")
      (node (ref "D17") (pin "A") (pinfunction "A_A") (pintype "passive"))
      (node (ref "Q25") (pin "2") (pinfunction "C_2") (pintype "passive"))
      (node (ref "REL18") (pin "2") (pintype "passive"))
    )
    (net (code "109") (name "/m18") (class "Default")
      (node (ref "D18") (pin "A") (pinfunction "A_A") (pintype "passive"))
      (node (ref "Q20") (pin "2") (pinfunction "C_2") (pintype "passive"))
      (node (ref "REL22") (pin "2") (pintype "passive"))
    )
    (net (code "110") (name "/m19") (class "Default")
      (node (ref "D19") (pin "A") (pinfunction "A_A") (pintype "passive"))
      (node (ref "Q19") (pin "2") (pinfunction "C_2") (pintype "passive"))
      (node (ref "REL1") (pin "2") (pintype "passive"))
    )
    (net (code "111") (name "/m20") (class "Default")
      (node (ref "D20") (pin "A") (pinfunction "A_A") (pintype "passive"))
      (node (ref "Q12") (pin "2") (pinfunction "C_2") (pintype "passive"))
      (node (ref "REL5") (pin "2") (pintype "passive"))
    )
    (net (code "112") (name "/m21") (class "Default")
      (node (ref "D21") (pin "A") (pinfunction "A_A") (pintype "passive"))
      (node (ref "Q5") (pin "2") (pinfunction "C_2") (pintype "passive"))
      (node (ref "REL9") (pin "2") (pintype "passive"))
    )
    (net (code "113") (name "/m22") (class "Default")
      (node (ref "D22") (pin "A") (pinfunction "A_A") (pintype "passive"))
      (node (ref "Q4") (pin "2") (pinfunction "C_2") (pintype "passive"))
      (node (ref "REL13") (pin "2") (pintype "passive"))
    )
    (net (code "114") (name "/m23") (class "Default")
      (node (ref "D23") (pin "A") (pinfunction "A_A") (pintype "passive"))
      (node (ref "Q3") (pin "2") (pinfunction "C_2") (pintype "passive"))
      (node (ref "REL17") (pin "2") (pintype "passive"))
    )
    (net (code "115") (name "/m24") (class "Default")
      (node (ref "D24") (pin "A") (pinfunction "A_A") (pintype "passive"))
      (node (ref "Q2") (pin "2") (pinfunction "C_2") (pintype "passive"))
      (node (ref "REL21") (pin "2") (pintype "passive"))
    )
    (net (code "116") (name "GND") (class "Default")
      (node (ref "C1") (pin "1") (pintype "passive"))
      (node (ref "C2") (pin "-") (pinfunction "-_-") (pintype "passive"))
      (node (ref "C3") (pin "1") (pintype "passive"))
      (node (ref "C4") (pin "1") (pintype "passive"))
      (node (ref "C5") (pin "-") (pinfunction "-_-") (pintype "passive"))
      (node (ref "C6") (pin "-") (pinfunction "-_-") (pintype "passive"))
      (node (ref "C7") (pin "-") (pinfunction "-_-") (pintype "passive"))
      (node (ref "C8") (pin "2") (pinfunction "2_2") (pintype "passive"))
      (node (ref "C9") (pin "2") (pinfunction "2_2") (pintype "passive"))
      (node (ref "D25") (pin "1") (pinfunction "A_1") (pintype "passive"))
      (node (ref "D26") (pin "1") (pinfunction "A_1") (pintype "passive"))
      (node (ref "D27") (pin "1") (pinfunction "A_1") (pintype "passive"))
      (node (ref "D28") (pin "1") (pinfunction "A_1") (pintype "passive"))
      (node (ref "D30") (pin "K") (pinfunction "K_K") (pintype "passive"))
      (node (ref "DZ1") (pin "1") (pintype "passive"))
      (node (ref "DZ2") (pin "1") (pintype "passive"))
      (node (ref "DZ3") (pin "1") (pintype "passive"))
      (node (ref "DZ4") (pin "1") (pintype "passive"))
      (node (ref "J1") (pin "1") (pinfunction "1_1") (pintype "passive"))
      (node (ref "J1") (pin "3") (pinfunction "3_3") (pintype "passive"))
      (node (ref "J2") (pin "3") (pinfunction "S_3") (pintype "input"))
      (node (ref "P1") (pin "1") (pinfunction "1_1") (pintype "passive"))
      (node (ref "P113") (pin "1") (pinfunction "1_1") (pintype "passive"))
      (node (ref "P2") (pin "7") (pinfunction "7_7") (pintype "passive"))
      (node (ref "Q1") (pin "1") (pinfunction "E_1") (pintype "passive"))
      (node (ref "Q10") (pin "1") (pinfunction "E_1") (pintype "passive"))
      (node (ref "Q11") (pin "1") (pinfunction "E_1") (pintype "passive"))
      (node (ref "Q12") (pin "1") (pinfunction "E_1") (pintype "passive"))
      (node (ref "Q13") (pin "1") (pinfunction "E_1") (pintype "passive"))
      (node (ref "Q14") (pin "1") (pinfunction "E_1") (pintype "passive"))
      (node (ref "Q15") (pin "1") (pinfunction "E_1") (pintype "passive"))
      (node (ref "Q16") (pin "1") (pinfunction "E_1") (pintype "passive"))
      (node (ref "Q17") (pin "1") (pinfunction "E_1") (pintype "passive"))
      (node (ref "Q18") (pin "1") (pinfunction "E_1") (pintype "passive"))
      (node (ref "Q19") (pin "1") (pinfunction "E_1") (pintype "passive"))
      (node (ref "Q2") (pin "1") (pinfunction "E_1") (pintype "passive"))
      (node (ref "Q20") (pin "1") (pinfunction "E_1") (pintype "passive"))
      (node (ref "Q21") (pin "1") (pinfunction "E_1") (pintype "passive"))
      (node (ref "Q22") (pin "1") (pinfunction "E_1") (pintype "passive"))
      (node (ref "Q23") (pin "1") (pinfunction "E_1") (pintype "passive"))
      (node (ref "Q24") (pin "1") (pinfunction "E_1") (pintype "passive"))
      (node (ref "Q25") (pin "1") (pinfunction "E_1") (pintype "passive"))
      (node (ref "Q3") (pin "1") (pinfunction "E_1") (pintype "passive"))
      (node (ref "Q4") (pin "1") (pinfunction "E_1") (pintype "passive"))
      (node (ref "Q5") (pin "1") (pinfunction "E_1") (pintype "passive"))
      (node (ref "Q6") (pin "1") (pinfunction "E_1") (pintype "passive"))
      (node (ref "Q7") (pin "1") (pinfunction "E_1") (pintype "passive"))
      (node (ref "Q8") (pin "1") (pinfunction "E_1") (pintype "passive"))
      (node (ref "Q9") (pin "1") (pinfunction "E_1") (pintype "passive"))
      (node (ref "U1") (pin "22") (pinfunction "GND_22") (pintype "power_in"))
      (node (ref "U1") (pin "53") (pinfunction "GND_53") (pintype "power_in"))
      (node (ref "U1") (pin "63") (pinfunction "GND_63") (pintype "power_in"))
      (node (ref "U2") (pin "2") (pinfunction "GND_2") (pintype "power_in"))
    )
    (net (code "117") (name "Net-(D29-PadK)") (class "Default")
      (node (ref "D29") (pin "K") (pinfunction "K_K") (pintype "passive"))
      (node (ref "D30") (pin "A") (pinfunction "A_A") (pintype "passive"))
    )
    (net (code "118") (name "Net-(D31-PadA)") (class "Default")
      (node (ref "D31") (pin "A") (pinfunction "A_A") (pintype "passive"))
      (node (ref "D32") (pin "A") (pinfunction "A_A") (pintype "passive"))
      (node (ref "S100") (pin "2") (pinfunction "2_2") (pintype "passive"))
    )
    (net (code "119") (name "Net-(Q1-B)") (class "Default")
      (node (ref "Q1") (pin "3") (pinfunction "B_3") (pintype "passive"))
      (node (ref "R2") (pin "2") (pintype "passive"))
    )
    (net (code "120") (name "Net-(Q1-C)") (class "Default")
      (node (ref "J1") (pin "16") (pinfunction "16_16") (pintype "passive"))
      (node (ref "Q1") (pin "2") (pinfunction "C_2") (pintype "passive"))
    )
    (net (code "121") (name "Net-(Q2-B)") (class "Default")
      (node (ref "Q2") (pin "3") (pinfunction "B_3") (pintype "passive"))
      (node (ref "R1") (pin "2") (pintype "passive"))
    )
    (net (code "122") (name "Net-(Q3-B)") (class "Default")
      (node (ref "Q3") (pin "3") (pinfunction "B_3") (pintype "passive"))
      (node (ref "R3") (pin "2") (pintype "passive"))
    )
    (net (code "123") (name "Net-(Q4-B)") (class "Default")
      (node (ref "Q4") (pin "3") (pinfunction "B_3") (pintype "passive"))
      (node (ref "R4") (pin "2") (pintype "passive"))
    )
    (net (code "124") (name "Net-(Q5-B)") (class "Default")
      (node (ref "Q5") (pin "3") (pinfunction "B_3") (pintype "passive"))
      (node (ref "R5") (pin "2") (pintype "passive"))
    )
    (net (code "125") (name "Net-(Q6-B)") (class "Default")
      (node (ref "Q6") (pin "3") (pinfunction "B_3") (pintype "passive"))
      (node (ref "R7") (pin "2") (pintype "passive"))
    )
    (net (code "126") (name "Net-(Q7-B)") (class "Default")
      (node (ref "Q7") (pin "3") (pinfunction "B_3") (pintype "passive"))
      (node (ref "R8") (pin "2") (pintype "passive"))
    )
    (net (code "127") (name "Net-(Q8-B)") (class "Default")
      (node (ref "Q8") (pin "3") (pinfunction "B_3") (pintype "passive"))
      (node (ref "R9") (pin "2") (pintype "passive"))
    )
    (net (code "128") (name "Net-(Q9-B)") (class "Default")
      (node (ref "Q9") (pin "3") (pinfunction "B_3") (pintype "passive"))
      (node (ref "R10") (pin "2") (pintype "passive"))
    )
    (net (code "129") (name "Net-(Q10-B)") (class "Default")
      (node (ref "Q10") (pin "3") (pinfunction "B_3") (pintype "passive"))
      (node (ref "R11") (pin "2") (pintype "passive"))
    )
    (net (code "130") (name "Net-(Q11-B)") (class "Default")
      (node (ref "Q11") (pin "3") (pinfunction "B_3") (pintype "passive"))
      (node (ref "R12") (pin "2") (pintype "passive"))
    )
    (net (code "131") (name "Net-(Q12-B)") (class "Default")
      (node (ref "Q12") (pin "3") (pinfunction "B_3") (pintype "passive"))
      (node (ref "R6") (pin "2") (pintype "passive"))
    )
    (net (code "132") (name "Net-(Q13-B)") (class "Default")
      (node (ref "Q13") (pin "3") (pinfunction "B_3") (pintype "passive"))
      (node (ref "R15") (pin "2") (pintype "passive"))
    )
    (net (code "133") (name "Net-(Q14-B)") (class "Default")
      (node (ref "Q14") (pin "3") (pinfunction "B_3") (pintype "passive"))
      (node (ref "R16") (pin "2") (pintype "passive"))
    )
    (net (code "134") (name "Net-(Q15-B)") (class "Default")
      (node (ref "Q15") (pin "3") (pinfunction "B_3") (pintype "passive"))
      (node (ref "R17") (pin "2") (pintype "passive"))
    )
    (net (code "135") (name "Net-(Q16-B)") (class "Default")
      (node (ref "Q16") (pin "3") (pinfunction "B_3") (pintype "passive"))
      (node (ref "R18") (pin "2") (pintype "passive"))
    )
    (net (code "136") (name "Net-(Q17-B)") (class "Default")
      (node (ref "Q17") (pin "3") (pinfunction "B_3") (pintype "passive"))
      (node (ref "R19") (pin "2") (pintype "passive"))
    )
    (net (code "137") (name "Net-(Q18-B)") (class "Default")
      (node (ref "Q18") (pin "3") (pinfunction "B_3") (pintype "passive"))
      (node (ref "R20") (pin "2") (pintype "passive"))
    )
    (net (code "138") (name "Net-(Q19-B)") (class "Default")
      (node (ref "Q19") (pin "3") (pinfunction "B_3") (pintype "passive"))
      (node (ref "R13") (pin "2") (pintype "passive"))
    )
    (net (code "139") (name "Net-(Q20-B)") (class "Default")
      (node (ref "Q20") (pin "3") (pinfunction "B_3") (pintype "passive"))
      (node (ref "R14") (pin "2") (pintype "passive"))
    )
    (net (code "140") (name "Net-(Q21-B)") (class "Default")
      (node (ref "Q21") (pin "3") (pinfunction "B_3") (pintype "passive"))
      (node (ref "R23") (pin "2") (pintype "passive"))
    )
    (net (code "141") (name "Net-(Q22-B)") (class "Default")
      (node (ref "Q22") (pin "3") (pinfunction "B_3") (pintype "passive"))
      (node (ref "R24") (pin "2") (pintype "passive"))
    )
    (net (code "142") (name "Net-(Q23-B)") (class "Default")
      (node (ref "Q23") (pin "3") (pinfunction "B_3") (pintype "passive"))
      (node (ref "R25") (pin "2") (pintype "passive"))
    )
    (net (code "143") (name "Net-(Q24-B)") (class "Default")
      (node (ref "Q24") (pin "3") (pinfunction "B_3") (pintype "passive"))
      (node (ref "R26") (pin "2") (pintype "passive"))
    )
    (net (code "144") (name "Net-(Q25-B)") (class "Default")
      (node (ref "Q25") (pin "3") (pinfunction "B_3") (pintype "passive"))
      (node (ref "R21") (pin "2") (pintype "passive"))
    )
    (net (code "145") (name "Net-(U1-PA0_(AD0))") (class "Default")
      (node (ref "J1") (pin "4") (pinfunction "4_4") (pintype "passive"))
      (node (ref "U1") (pin "51") (pinfunction "PA0_(AD0)_51") (pintype "bidirectional"))
    )
    (net (code "146") (name "Net-(U1-PA1_(AD1))") (class "Default")
      (node (ref "J1") (pin "5") (pinfunction "5_5") (pintype "passive"))
      (node (ref "U1") (pin "50") (pinfunction "PA1_(AD1)_50") (pintype "bidirectional"))
    )
    (net (code "147") (name "Net-(U1-PA2_(AD2))") (class "Default")
      (node (ref "J1") (pin "6") (pinfunction "6_6") (pintype "passive"))
      (node (ref "U1") (pin "49") (pinfunction "PA2_(AD2)_49") (pintype "bidirectional"))
    )
    (net (code "148") (name "Net-(U1-PA3_(AD3))") (class "Default")
      (node (ref "R2") (pin "1") (pintype "passive"))
      (node (ref "U1") (pin "48") (pinfunction "PA3_(AD3)_48") (pintype "bidirectional"))
    )
    (net (code "149") (name "Net-(U1-PA4_(AD4))") (class "Default")
      (node (ref "J1") (pin "11") (pinfunction "11_11") (pintype "passive"))
      (node (ref "U1") (pin "47") (pinfunction "PA4_(AD4)_47") (pintype "bidirectional"))
    )
    (net (code "150") (name "Net-(U1-PA5_(AD5))") (class "Default")
      (node (ref "J1") (pin "12") (pinfunction "12_12") (pintype "passive"))
      (node (ref "U1") (pin "46") (pinfunction "PA5_(AD5)_46") (pintype "bidirectional"))
    )
    (net (code "151") (name "Net-(U1-PA6_(AD6))") (class "Default")
      (node (ref "J1") (pin "13") (pinfunction "13_13") (pintype "passive"))
      (node (ref "U1") (pin "45") (pinfunction "PA6_(AD6)_45") (pintype "bidirectional"))
    )
    (net (code "152") (name "Net-(U1-PA7_(AD7))") (class "Default")
      (node (ref "J1") (pin "14") (pinfunction "14_14") (pintype "passive"))
      (node (ref "U1") (pin "44") (pinfunction "PA7_(AD7)_44") (pintype "bidirectional"))
    )
    (net (code "153") (name "Net-(U1-XTAL1)") (class "Default")
      (node (ref "C4") (pin "2") (pintype "passive"))
      (node (ref "U1") (pin "24") (pinfunction "XTAL1_24") (pintype "passive"))
      (node (ref "X1") (pin "1") (pintype "passive"))
    )
    (net (code "154") (name "Net-(U1-XTAL2)") (class "Default")
      (node (ref "C3") (pin "2") (pintype "passive"))
      (node (ref "U1") (pin "23") (pinfunction "XTAL2_23") (pintype "passive"))
      (node (ref "X1") (pin "2") (pintype "passive"))
    )
    (net (code "155") (name "VCC") (class "Default")
      (node (ref "C1") (pin "2") (pintype "passive"))
      (node (ref "C2") (pin "+") (pinfunction "+_+") (pintype "passive"))
      (node (ref "C6") (pin "+") (pinfunction "+_+") (pintype "passive"))
      (node (ref "C7") (pin "+") (pinfunction "+_+") (pintype "passive"))
      (node (ref "C8") (pin "1") (pinfunction "1_1") (pintype "passive"))
      (node (ref "C9") (pin "1") (pinfunction "1_1") (pintype "passive"))
      (node (ref "D25") (pin "2") (pinfunction "K_2") (pintype "passive"))
      (node (ref "D26") (pin "2") (pinfunction "K_2") (pintype "passive"))
      (node (ref "D27") (pin "2") (pinfunction "K_2") (pintype "passive"))
      (node (ref "D28") (pin "2") (pinfunction "K_2") (pintype "passive"))
      (node (ref "D29") (pin "A") (pinfunction "A_A") (pintype "passive"))
      (node (ref "DZ1") (pin "2") (pintype "passive"))
      (node (ref "DZ2") (pin "2") (pintype "passive"))
      (node (ref "DZ3") (pin "2") (pintype "passive"))
      (node (ref "DZ4") (pin "2") (pintype "passive"))
      (node (ref "J1") (pin "15") (pinfunction "15_15") (pintype "passive"))
      (node (ref "J1") (pin "2") (pinfunction "2_2") (pintype "passive"))
      (node (ref "P1") (pin "2") (pinfunction "2_2") (pintype "passive"))
      (node (ref "P113") (pin "6") (pinfunction "6_6") (pintype "passive"))
      (node (ref "R22") (pin "1") (pintype "passive"))
      (node (ref "U1") (pin "21") (pinfunction "VCC_21") (pintype "power_in"))
      (node (ref "U1") (pin "52") (pinfunction "VCC_52") (pintype "power_in"))
      (node (ref "U1") (pin "62") (pinfunction "AREF_62") (pintype "passive"))
      (node (ref "U1") (pin "64") (pinfunction "AVCC_64") (pintype "power_in"))
      (node (ref "U2") (pin "3") (pinfunction "+5V_3") (pintype "power_in"))
    )
    (net (code "156") (name "unconnected-(J1-Pad7)") (class "Default")
      (node (ref "J1") (pin "7") (pinfunction "7_7") (pintype "passive"))
    )
    (net (code "157") (name "unconnected-(J1-Pad8)") (class "Default")
      (node (ref "J1") (pin "8") (pinfunction "8_8") (pintype "passive"))
    )
    (net (code "158") (name "unconnected-(J1-Pad9)") (class "Default")
      (node (ref "J1") (pin "9") (pinfunction "9_9") (pintype "passive"))
    )
    (net (code "159") (name "unconnected-(J1-Pad10)") (class "Default")
      (node (ref "J1") (pin "10") (pinfunction "10_10") (pintype "passive"))
    )
    (net (code "160") (name "unconnected-(REL1-Pad6)") (class "Default")
      (node (ref "REL1") (pin "6") (pintype "passive"))
    )
    (net (code "161") (name "unconnected-(REL1-Pad8)") (class "Default")
      (node (ref "REL1") (pin "8") (pintype "passive"))
    )
    (net (code "162") (name "unconnected-(REL2-Pad6)") (class "Default")
      (node (ref "REL2") (pin "6") (pintype "passive"))
    )
    (net (code "163") (name "unconnected-(REL2-Pad8)") (class "Default")
      (node (ref "REL2") (pin "8") (pintype "passive"))
    )
    (net (code "164") (name "unconnected-(REL3-Pad6)") (class "Default")
      (node (ref "REL3") (pin "6") (pintype "passive"))
    )
    (net (code "165") (name "unconnected-(REL3-Pad8)") (class "Default")
      (node (ref "REL3") (pin "8") (pintype "passive"))
    )
    (net (code "166") (name "unconnected-(REL4-Pad6)") (class "Default")
      (node (ref "REL4") (pin "6") (pintype "passive"))
    )
    (net (code "167") (name "unconnected-(REL4-Pad8)") (class "Default")
      (node (ref "REL4") (pin "8") (pintype "passive"))
    )
    (net (code "168") (name "unconnected-(REL5-Pad6)") (class "Default")
      (node (ref "REL5") (pin "6") (pintype "passive"))
    )
    (net (code "169") (name "unconnected-(REL5-Pad8)") (class "Default")
      (node (ref "REL5") (pin "8") (pintype "passive"))
    )
    (net (code "170") (name "unconnected-(REL6-Pad6)") (class "Default")
      (node (ref "REL6") (pin "6") (pintype "passive"))
    )
    (net (code "171") (name "unconnected-(REL6-Pad8)") (class "Default")
      (node (ref "REL6") (pin "8") (pintype "passive"))
    )
    (net (code "172") (name "unconnected-(REL7-Pad6)") (class "Default")
      (node (ref "REL7") (pin "6") (pintype "passive"))
    )
    (net (code "173") (name "unconnected-(REL7-Pad8)") (class "Default")
      (node (ref "REL7") (pin "8") (pintype "passive"))
    )
    (net (code "174") (name "unconnected-(REL8-Pad6)") (class "Default")
      (node (ref "REL8") (pin "6") (pintype "passive"))
    )
    (net (code "175") (name "unconnected-(REL8-Pad8)") (class "Default")
      (node (ref "REL8") (pin "8") (pintype "passive"))
    )
    (net (code "176") (name "unconnected-(REL9-Pad6)") (class "Default")
      (node (ref "REL9") (pin "6") (pintype "passive"))
    )
    (net (code "177") (name "unconnected-(REL9-Pad8)") (class "Default")
      (node (ref "REL9") (pin "8") (pintype "passive"))
    )
    (net (code "178") (name "unconnected-(REL10-Pad6)") (class "Default")
      (node (ref "REL10") (pin "6") (pintype "passive"))
    )
    (net (code "179") (name "unconnected-(REL10-Pad8)") (class "Default")
      (node (ref "REL10") (pin "8") (pintype "passive"))
    )
    (net (code "180") (name "unconnected-(REL11-Pad6)") (class "Default")
      (node (ref "REL11") (pin "6") (pintype "passive"))
    )
    (net (code "181") (name "unconnected-(REL11-Pad8)") (class "Default")
      (node (ref "REL11") (pin "8") (pintype "passive"))
    )
    (net (code "182") (name "unconnected-(REL12-Pad6)") (class "Default")
      (node (ref "REL12") (pin "6") (pintype "passive"))
    )
    (net (code "183") (name "unconnected-(REL12-Pad8)") (class "Default")
      (node (ref "REL12") (pin "8") (pintype "passive"))
    )
    (net (code "184") (name "unconnected-(REL13-Pad6)") (class "Default")
      (node (ref "REL13") (pin "6") (pintype "passive"))
    )
    (net (code "185") (name "unconnected-(REL13-Pad8)") (class "Default")
      (node (ref "REL13") (pin "8") (pintype "passive"))
    )
    (net (code "186") (name "unconnected-(REL14-Pad6)") (class "Default")
      (node (ref "REL14") (pin "6") (pintype "passive"))
    )
    (net (code "187") (name "unconnected-(REL14-Pad8)") (class "Default")
      (node (ref "REL14") (pin "8") (pintype "passive"))
    )
    (net (code "188") (name "unconnected-(REL15-Pad6)") (class "Default")
      (node (ref "REL15") (pin "6") (pintype "passive"))
    )
    (net (code "189") (name "unconnected-(REL15-Pad8)") (class "Default")
      (node (ref "REL15") (pin "8") (pintype "passive"))
    )
    (net (code "190") (name "unconnected-(REL16-Pad6)") (class "Default")
      (node (ref "REL16") (pin "6") (pintype "passive"))
    )
    (net (code "191") (name "unconnected-(REL16-Pad8)") (class "Default")
      (node (ref "REL16") (pin "8") (pintype "passive"))
    )
    (net (code "192") (name "unconnected-(REL17-Pad6)") (class "Default")
      (node (ref "REL17") (pin "6") (pintype "passive"))
    )
    (net (code "193") (name "unconnected-(REL17-Pad8)") (class "Default")
      (node (ref "REL17") (pin "8") (pintype "passive"))
    )
    (net (code "194") (name "unconnected-(REL18-Pad6)") (class "Default")
      (node (ref "REL18") (pin "6") (pintype "passive"))
    )
    (net (code "195") (name "unconnected-(REL18-Pad8)") (class "Default")
      (node (ref "REL18") (pin "8") (pintype "passive"))
    )
    (net (code "196") (name "unconnected-(REL19-Pad6)") (class "Default")
      (node (ref "REL19") (pin "6") (pintype "passive"))
    )
    (net (code "197") (name "unconnected-(REL19-Pad8)") (class "Default")
      (node (ref "REL19") (pin "8") (pintype "passive"))
    )
    (net (code "198") (name "unconnected-(REL20-Pad6)") (class "Default")
      (node (ref "REL20") (pin "6") (pintype "passive"))
    )
    (net (code "199") (name "unconnected-(REL20-Pad8)") (class "Default")
      (node (ref "REL20") (pin "8") (pintype "passive"))
    )
    (net (code "200") (name "unconnected-(REL21-Pad6)") (class "Default")
      (node (ref "REL21") (pin "6") (pintype "passive"))
    )
    (net (code "201") (name "unconnected-(REL21-Pad8)") (class "Default")
      (node (ref "REL21") (pin "8") (pintype "passive"))
    )
    (net (code "202") (name "unconnected-(REL22-Pad6)") (class "Default")
      (node (ref "REL22") (pin "6") (pintype "passive"))
    )
    (net (code "203") (name "unconnected-(REL22-Pad8)") (class "Default")
      (node (ref "REL22") (pin "8") (pintype "passive"))
    )
    (net (code "204") (name "unconnected-(REL23-Pad6)") (class "Default")
      (node (ref "REL23") (pin "6") (pintype "passive"))
    )
    (net (code "205") (name "unconnected-(REL23-Pad8)") (class "Default")
      (node (ref "REL23") (pin "8") (pintype "passive"))
    )
    (net (code "206") (name "unconnected-(REL24-Pad6)") (class "Default")
      (node (ref "REL24") (pin "6") (pintype "passive"))
    )
    (net (code "207") (name "unconnected-(REL24-Pad8)") (class "Default")
      (node (ref "REL24") (pin "8") (pintype "passive"))
    )
    (net (code "208") (name "unconnected-(S100-Pad1)") (class "Default")
      (node (ref "S100") (pin "1") (pinfunction "1_1") (pintype "passive"))
    )
    (net (code "209") (name "unconnected-(T9-Pad2)") (class "Default")
      (node (ref "T9") (pin "2") (pintype "passive"))
    )
    (net (code "210") (name "unconnected-(U1-PC6_(A14)-Pad41)") (class "Default")
      (node (ref "U1") (pin "41") (pinfunction "PC6_(A14)_41") (pintype "bidirectional"))
    )
    (net (code "211") (name "unconnected-(U1-PC7_(A15)-Pad42)") (class "Default")
      (node (ref "U1") (pin "42") (pinfunction "PC7_(A15)_42") (pintype "bidirectional"))
    )
    (net (code "212") (name "unconnected-(U1-PG0_(~{WR})-Pad33)") (class "Default")
      (node (ref "U1") (pin "33") (pinfunction "PG0_(~{WR})_33") (pintype "bidirectional"))
    )
    (net (code "213") (name "unconnected-(U1-PG1_(~{RD})-Pad34)") (class "Default")
      (node (ref "U1") (pin "34") (pinfunction "PG1_(~{RD})_34") (pintype "bidirectional"))
    )
    (net (code "214") (name "unconnected-(U1-PG2_(ALE)-Pad43)") (class "Default")
      (node (ref "U1") (pin "43") (pinfunction "PG2_(ALE)_43") (pintype "bidirectional"))
    )
    (net (code "215") (name "unconnected-(U1-PG3{slash}TOSC2-Pad18)") (class "Default")
      (node (ref "U1") (pin "18") (pinfunction "PG3/TOSC2_18") (pintype "bidirectional"))
    )
    (net (code "216") (name "unconnected-(U1-PG4{slash}TOSC1-Pad19)") (class "Default")
      (node (ref "U1") (pin "19") (pinfunction "PG4/TOSC1_19") (pintype "bidirectional"))
    )
    (net (code "217") (name "unconnected-(U1-~{PEN}-Pad1)") (class "Default")
      (node (ref "U1") (pin "1") (pinfunction "~{PEN}_1") (pintype "input"))
    )
  )
)
